# TOP.net
KiCad netlist of a schematic drawn in Altium Designer
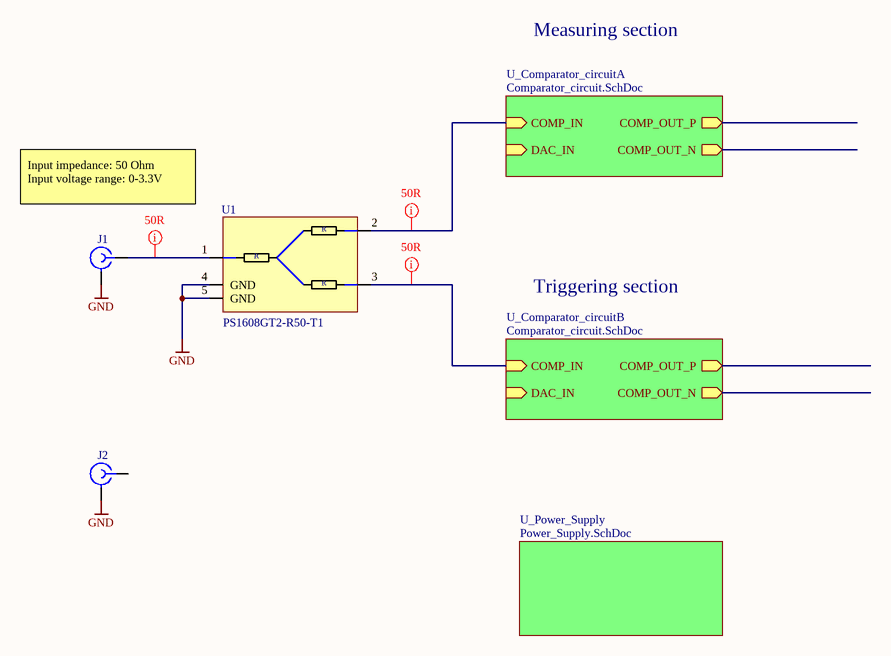
[diagram p0: TOP.SchDoc]

(export (version "E")
  (design (tool "Eeschema 10.0.6"))
  (components
    (comp (ref "J1")
      (value "CONSMA020.062-G")
      (description "Coaxial Connectors SMA, Edge Mount, Female Receptacle, 0.062\" PCB Mount, Gold")
      (libsource (lib "") (part "Coax_1Female_1Shield_1"))
    )
    (comp (ref "J2")
      (value "CONSMA020.062-G")
      (description "Coaxial Connectors SMA, Edge Mount, Female Receptacle, 0.062\" PCB Mount, Gold")
      (libsource (lib "Connectors") (part "Coax_1Female_1Shield"))
    )
    (comp (ref "U1")
      (value "PS1608GT2-R50-T1")
      (description "Signal Conditioning 50 ohm 2 terminal Power Splitter")
      (libsource (lib "Resistors") (part "PSXXXXGT2-R50"))
    )
  )
  (nets
    (net (code "1") (name "/COMP_IN") (class "Default")
      (node (ref "U1") (pin "3") (pinfunction "3_3") (pintype "passive"))
    )
    (net (code "2") (name "/COMP_IN_1") (class "Default")
      (node (ref "U1") (pin "2") (pinfunction "2_2") (pintype "passive"))
    )
    (net (code "9") (name "GND") (class "Default")
      (node (ref "J1") (pin "2") (pinfunction "2_2") (pintype "passive"))
      (node (ref "U1") (pin "4") (pinfunction "GND_4") (pintype "passive"))
      (node (ref "U1") (pin "5") (pinfunction "GND_5") (pintype "passive"))
    )
    (net (code "10") (name "Net-(J1-Pad1)") (class "Default")
      (node (ref "J1") (pin "1") (pinfunction "1_1") (pintype "passive"))
      (node (ref "U1") (pin "1") (pinfunction "1_1") (pintype "passive"))
    )
    (net (code "11") (name "unconnected-(J2-Pad1)") (class "Default")
      (node (ref "J2") (pin "1") (pinfunction "1_1") (pintype "passive"))
    )
    (net (code "12") (name "unconnected-(J2-Pad2)") (class "Default")
      (node (ref "J2") (pin "2") (pinfunction "2_2") (pintype "power_in"))
    )
  )
)
